# EncoderR1.net
KiCad netlist of a schematic drawn in EAGLE
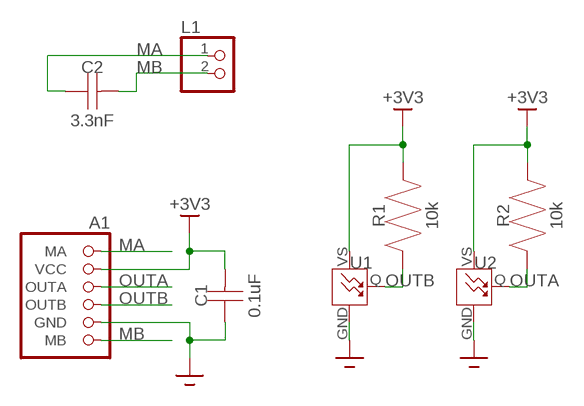
[diagram p0: schematic, sheet 1]

(export (version "E")
  (design (tool "Eeschema 10.0.6"))
  (components
    (comp (ref "A1")
      (value "ENCODER")
      (footprint "eagle-import:ENCODER-TAB")
      (libsource (lib "eagle-import") (part "ENCODER"))
    )
    (comp (ref "C1")
      (value "0.1uF")
      (footprint "eagle-import:0603")
      (libsource (lib "eagle-import") (part "CAPACITOR0603"))
    )
    (comp (ref "C2")
      (value "3.3nF")
      (footprint "eagle-import:0603")
      (libsource (lib "eagle-import") (part "CAPACITOR0603"))
    )
    (comp (ref "L1")
      (value "MOTOR")
      (footprint "eagle-import:MOTOR")
      (libsource (lib "eagle-import") (part "MOTOR"))
    )
    (comp (ref "R1")
      (value "10k")
      (footprint "eagle-import:0603")
      (libsource (lib "eagle-import") (part "RESISTOR0603"))
    )
    (comp (ref "R2")
      (value "10k")
      (footprint "eagle-import:0603")
      (libsource (lib "eagle-import") (part "RESISTOR0603"))
    )
    (comp (ref "U1")
      (value "TLE49462KHTSA1")
      (footprint "eagle-import:TLE49462KHTSA1")
      (libsource (lib "eagle-import") (part "TLE49462KHTSA1"))
    )
    (comp (ref "U2")
      (value "TLE49462KHTSA1")
      (footprint "eagle-import:TLE49462KHTSA1")
      (libsource (lib "eagle-import") (part "TLE49462KHTSA1"))
    )
  )
  (nets
    (net (code "1") (name "+3V3") (class "Default")
      (node (ref "A1") (pin "2") (pinfunction "VCC_2") (pintype "power_in"))
      (node (ref "C1") (pin "2") (pinfunction "P$2_2") (pintype "passive"))
      (node (ref "R1") (pin "2") (pinfunction "P$2_2") (pintype "passive"))
      (node (ref "R2") (pin "2") (pinfunction "P$2_2") (pintype "passive"))
      (node (ref "U1") (pin "VS") (pinfunction "VS_VS") (pintype "power_in"))
      (node (ref "U2") (pin "VS") (pinfunction "VS_VS") (pintype "power_in"))
    )
    (net (code "2") (name "/MA") (class "Default")
      (node (ref "A1") (pin "1") (pinfunction "MA_1") (pintype "input"))
      (node (ref "C2") (pin "1") (pinfunction "P$1_1") (pintype "passive"))
      (node (ref "L1") (pin "1") (pinfunction "1_1") (pintype "passive"))
    )
    (net (code "3") (name "/MB") (class "Default")
      (node (ref "A1") (pin "6") (pinfunction "MB_6") (pintype "input"))
      (node (ref "C2") (pin "2") (pinfunction "P$2_2") (pintype "passive"))
      (node (ref "L1") (pin "2") (pinfunction "2_2") (pintype "passive"))
    )
    (net (code "4") (name "/OUTA") (class "Default")
      (node (ref "A1") (pin "3") (pinfunction "OUTA_3") (pintype "output"))
      (node (ref "R2") (pin "1") (pinfunction "P$1_1") (pintype "passive"))
      (node (ref "U2") (pin "Q") (pinfunction "Q_Q") (pintype "output"))
    )
    (net (code "5") (name "/OUTB") (class "Default")
      (node (ref "A1") (pin "4") (pinfunction "OUTB_4") (pintype "output"))
      (node (ref "R1") (pin "1") (pinfunction "P$1_1") (pintype "passive"))
      (node (ref "U1") (pin "Q") (pinfunction "Q_Q") (pintype "output"))
    )
    (net (code "6") (name "GND") (class "Default")
      (node (ref "A1") (pin "5") (pinfunction "GND_5") (pintype "passive"))
      (node (ref "C1") (pin "1") (pinfunction "P$1_1") (pintype "passive"))
      (node (ref "U1") (pin "GND") (pinfunction "GND_GND") (pintype "passive"))
      (node (ref "U2") (pin "GND") (pinfunction "GND_GND") (pintype "passive"))
    )
  )
)
